# rct_cntrl_brd.net
KiCad netlist of a schematic drawn in EAGLE
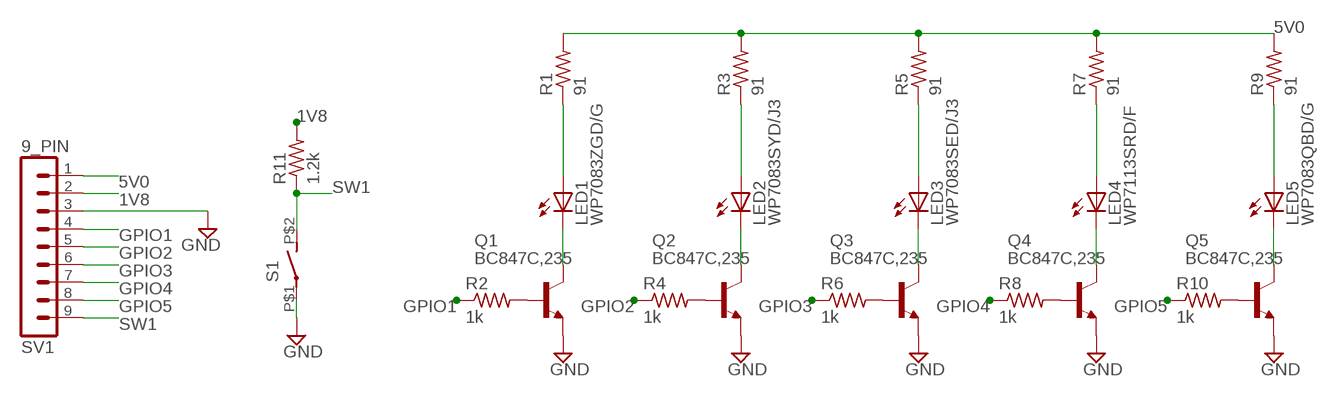
[diagram p0: schematic, sheet 1]

(export (version "E")
  (design (tool "Eeschema 10.0.6"))
  (components
    (comp (ref "LED1")
      (value "WP7083ZGD/G")
      (footprint "eagle-import:LED5MM")
      (libsource (lib "eagle-import") (part "LED5MM"))
    )
    (comp (ref "LED2")
      (value "WP7083SYD/J3")
      (footprint "eagle-import:LED5MM")
      (libsource (lib "eagle-import") (part "LED5MM"))
    )
    (comp (ref "LED3")
      (value "WP7083SED/J3")
      (footprint "eagle-import:LED5MM")
      (libsource (lib "eagle-import") (part "LED5MM"))
    )
    (comp (ref "LED4")
      (value "WP7113SRD/F")
      (footprint "eagle-import:LED5MM")
      (libsource (lib "eagle-import") (part "LED5MM"))
    )
    (comp (ref "LED5")
      (value "WP7083QBD/G")
      (footprint "eagle-import:LED5MM")
      (libsource (lib "eagle-import") (part "LED5MM"))
    )
    (comp (ref "Q1")
      (value "BC847C,235")
      (footprint "eagle-import:SOT23-BEC")
      (libsource (lib "eagle-import") (part "-NPN-SOT23-BECBC847C"))
    )
    (comp (ref "Q2")
      (value "BC847C,235")
      (footprint "eagle-import:SOT23-BEC")
      (libsource (lib "eagle-import") (part "-NPN-SOT23-BECBC847C"))
    )
    (comp (ref "Q3")
      (value "BC847C,235")
      (footprint "eagle-import:SOT23-BEC")
      (libsource (lib "eagle-import") (part "-NPN-SOT23-BECBC847C"))
    )
    (comp (ref "Q4")
      (value "BC847C,235")
      (footprint "eagle-import:SOT23-BEC")
      (libsource (lib "eagle-import") (part "-NPN-SOT23-BECBC847C"))
    )
    (comp (ref "Q5")
      (value "BC847C,235")
      (footprint "eagle-import:SOT23-BEC")
      (libsource (lib "eagle-import") (part "-NPN-SOT23-BECBC847C"))
    )
    (comp (ref "R1")
      (value "91")
      (footprint "eagle-import:R0603")
      (libsource (lib "eagle-import") (part "R-US_R0603"))
    )
    (comp (ref "R2")
      (value "1k")
      (footprint "eagle-import:R0603")
      (libsource (lib "eagle-import") (part "R-US_R0603"))
    )
    (comp (ref "R3")
      (value "91")
      (footprint "eagle-import:R0603")
      (libsource (lib "eagle-import") (part "R-US_R0603"))
    )
    (comp (ref "R4")
      (value "1k")
      (footprint "eagle-import:R0603")
      (libsource (lib "eagle-import") (part "R-US_R0603"))
    )
    (comp (ref "R5")
      (value "91")
      (footprint "eagle-import:R0603")
      (libsource (lib "eagle-import") (part "R-US_R0603"))
    )
    (comp (ref "R6")
      (value "1k")
      (footprint "eagle-import:R0603")
      (libsource (lib "eagle-import") (part "R-US_R0603"))
    )
    (comp (ref "R7")
      (value "91")
      (footprint "eagle-import:R0603")
      (libsource (lib "eagle-import") (part "R-US_R0603"))
    )
    (comp (ref "R8")
      (value "1k")
      (footprint "eagle-import:R0603")
      (libsource (lib "eagle-import") (part "R-US_R0603"))
    )
    (comp (ref "R9")
      (value "91")
      (footprint "eagle-import:R0603")
      (libsource (lib "eagle-import") (part "R-US_R0603"))
    )
    (comp (ref "R10")
      (value "1k")
      (footprint "eagle-import:R0603")
      (libsource (lib "eagle-import") (part "R-US_R0603"))
    )
    (comp (ref "R11")
      (value "1.2k")
      (footprint "eagle-import:R0603")
      (libsource (lib "eagle-import") (part "R-US_R0603"))
    )
    (comp (ref "S1")
      (value "TMS6T5B2M2RE")
      (footprint "eagle-import:PC_THRU_HOLE_2")
      (libsource (lib "eagle-import") (part "TMS6T5B2M2RE"))
    )
    (comp (ref "SV1")
      (value "9_PIN")
      (footprint "eagle-import:MA09-1")
      (libsource (lib "eagle-import") (part "MA09-1"))
    )
  )
  (nets
    (net (code "1") (name "/1V8") (class "Default")
      (node (ref "R11") (pin "2") (pinfunction "2_2") (pintype "passive"))
      (node (ref "SV1") (pin "2") (pinfunction "2_2") (pintype "passive"))
    )
    (net (code "2") (name "/5V0") (class "Default")
      (node (ref "R1") (pin "2") (pinfunction "2_2") (pintype "passive"))
      (node (ref "R3") (pin "2") (pinfunction "2_2") (pintype "passive"))
      (node (ref "R5") (pin "2") (pinfunction "2_2") (pintype "passive"))
      (node (ref "R7") (pin "2") (pinfunction "2_2") (pintype "passive"))
      (node (ref "R9") (pin "2") (pinfunction "2_2") (pintype "passive"))
      (node (ref "SV1") (pin "1") (pinfunction "1_1") (pintype "passive"))
    )
    (net (code "3") (name "/GPIO1") (class "Default")
      (node (ref "R2") (pin "1") (pinfunction "1_1") (pintype "passive"))
      (node (ref "SV1") (pin "4") (pinfunction "4_4") (pintype "passive"))
    )
    (net (code "4") (name "/GPIO2") (class "Default")
      (node (ref "R4") (pin "1") (pinfunction "1_1") (pintype "passive"))
      (node (ref "SV1") (pin "5") (pinfunction "5_5") (pintype "passive"))
    )
    (net (code "5") (name "/GPIO3") (class "Default")
      (node (ref "R6") (pin "1") (pinfunction "1_1") (pintype "passive"))
      (node (ref "SV1") (pin "6") (pinfunction "6_6") (pintype "passive"))
    )
    (net (code "6") (name "/GPIO4") (class "Default")
      (node (ref "R8") (pin "1") (pinfunction "1_1") (pintype "passive"))
      (node (ref "SV1") (pin "7") (pinfunction "7_7") (pintype "passive"))
    )
    (net (code "7") (name "/GPIO5") (class "Default")
      (node (ref "R10") (pin "1") (pinfunction "1_1") (pintype "passive"))
      (node (ref "SV1") (pin "8") (pinfunction "8_8") (pintype "passive"))
    )
    (net (code "8") (name "/SW1") (class "Default")
      (node (ref "R11") (pin "1") (pinfunction "1_1") (pintype "passive"))
      (node (ref "S1") (pin "P$2") (pinfunction "S_P$2") (pintype "passive"))
      (node (ref "SV1") (pin "9") (pinfunction "9_9") (pintype "passive"))
    )
    (net (code "9") (name "GND") (class "Default")
      (node (ref "Q1") (pin "E") (pinfunction "E_E") (pintype "passive"))
      (node (ref "Q2") (pin "E") (pinfunction "E_E") (pintype "passive"))
      (node (ref "Q3") (pin "E") (pinfunction "E_E") (pintype "passive"))
      (node (ref "Q4") (pin "E") (pinfunction "E_E") (pintype "passive"))
      (node (ref "Q5") (pin "E") (pinfunction "E_E") (pintype "passive"))
      (node (ref "S1") (pin "P$1") (pinfunction "P_P$1") (pintype "passive"))
      (node (ref "SV1") (pin "3") (pinfunction "3_3") (pintype "passive"))
    )
    (net (code "10") (name "Net-(LED1-C)") (class "Default")
      (node (ref "LED1") (pin "K") (pinfunction "C_K") (pintype "passive"))
      (node (ref "Q1") (pin "C") (pinfunction "C_C") (pintype "passive"))
    )
    (net (code "11") (name "Net-(LED1-PadA)") (class "Default")
      (node (ref "LED1") (pin "A") (pinfunction "A_A") (pintype "passive"))
      (node (ref "R1") (pin "1") (pinfunction "1_1") (pintype "passive"))
    )
    (net (code "12") (name "Net-(LED2-C)") (class "Default")
      (node (ref "LED2") (pin "K") (pinfunction "C_K") (pintype "passive"))
      (node (ref "Q2") (pin "C") (pinfunction "C_C") (pintype "passive"))
    )
    (net (code "13") (name "Net-(LED2-PadA)") (class "Default")
      (node (ref "LED2") (pin "A") (pinfunction "A_A") (pintype "passive"))
      (node (ref "R3") (pin "1") (pinfunction "1_1") (pintype "passive"))
    )
    (net (code "14") (name "Net-(LED3-C)") (class "Default")
      (node (ref "LED3") (pin "K") (pinfunction "C_K") (pintype "passive"))
      (node (ref "Q3") (pin "C") (pinfunction "C_C") (pintype "passive"))
    )
    (net (code "15") (name "Net-(LED3-PadA)") (class "Default")
      (node (ref "LED3") (pin "A") (pinfunction "A_A") (pintype "passive"))
      (node (ref "R5") (pin "1") (pinfunction "1_1") (pintype "passive"))
    )
    (net (code "16") (name "Net-(LED4-C)") (class "Default")
      (node (ref "LED4") (pin "K") (pinfunction "C_K") (pintype "passive"))
      (node (ref "Q4") (pin "C") (pinfunction "C_C") (pintype "passive"))
    )
    (net (code "17") (name "Net-(LED4-PadA)") (class "Default")
      (node (ref "LED4") (pin "A") (pinfunction "A_A") (pintype "passive"))
      (node (ref "R7") (pin "1") (pinfunction "1_1") (pintype "passive"))
    )
    (net (code "18") (name "Net-(LED5-C)") (class "Default")
      (node (ref "LED5") (pin "K") (pinfunction "C_K") (pintype "passive"))
      (node (ref "Q5") (pin "C") (pinfunction "C_C") (pintype "passive"))
    )
    (net (code "19") (name "Net-(LED5-PadA)") (class "Default")
      (node (ref "LED5") (pin "A") (pinfunction "A_A") (pintype "passive"))
      (node (ref "R9") (pin "1") (pinfunction "1_1") (pintype "passive"))
    )
    (net (code "20") (name "Net-(Q1-PadB)") (class "Default")
      (node (ref "Q1") (pin "B") (pinfunction "B_B") (pintype "passive"))
      (node (ref "R2") (pin "2") (pinfunction "2_2") (pintype "passive"))
    )
    (net (code "21") (name "Net-(Q2-PadB)") (class "Default")
      (node (ref "Q2") (pin "B") (pinfunction "B_B") (pintype "passive"))
      (node (ref "R4") (pin "2") (pinfunction "2_2") (pintype "passive"))
    )
    (net (code "22") (name "Net-(Q3-PadB)") (class "Default")
      (node (ref "Q3") (pin "B") (pinfunction "B_B") (pintype "passive"))
      (node (ref "R6") (pin "2") (pinfunction "2_2") (pintype "passive"))
    )
    (net (code "23") (name "Net-(Q4-PadB)") (class "Default")
      (node (ref "Q4") (pin "B") (pinfunction "B_B") (pintype "passive"))
      (node (ref "R8") (pin "2") (pinfunction "2_2") (pintype "passive"))
    )
    (net (code "24") (name "Net-(Q5-PadB)") (class "Default")
      (node (ref "Q5") (pin "B") (pinfunction "B_B") (pintype "passive"))
      (node (ref "R10") (pin "2") (pinfunction "2_2") (pintype "passive"))
    )
  )
)
